# MH-M38-Bluetooth-audio-receiver-circuit.net
KiCad netlist of a schematic drawn in EAGLE
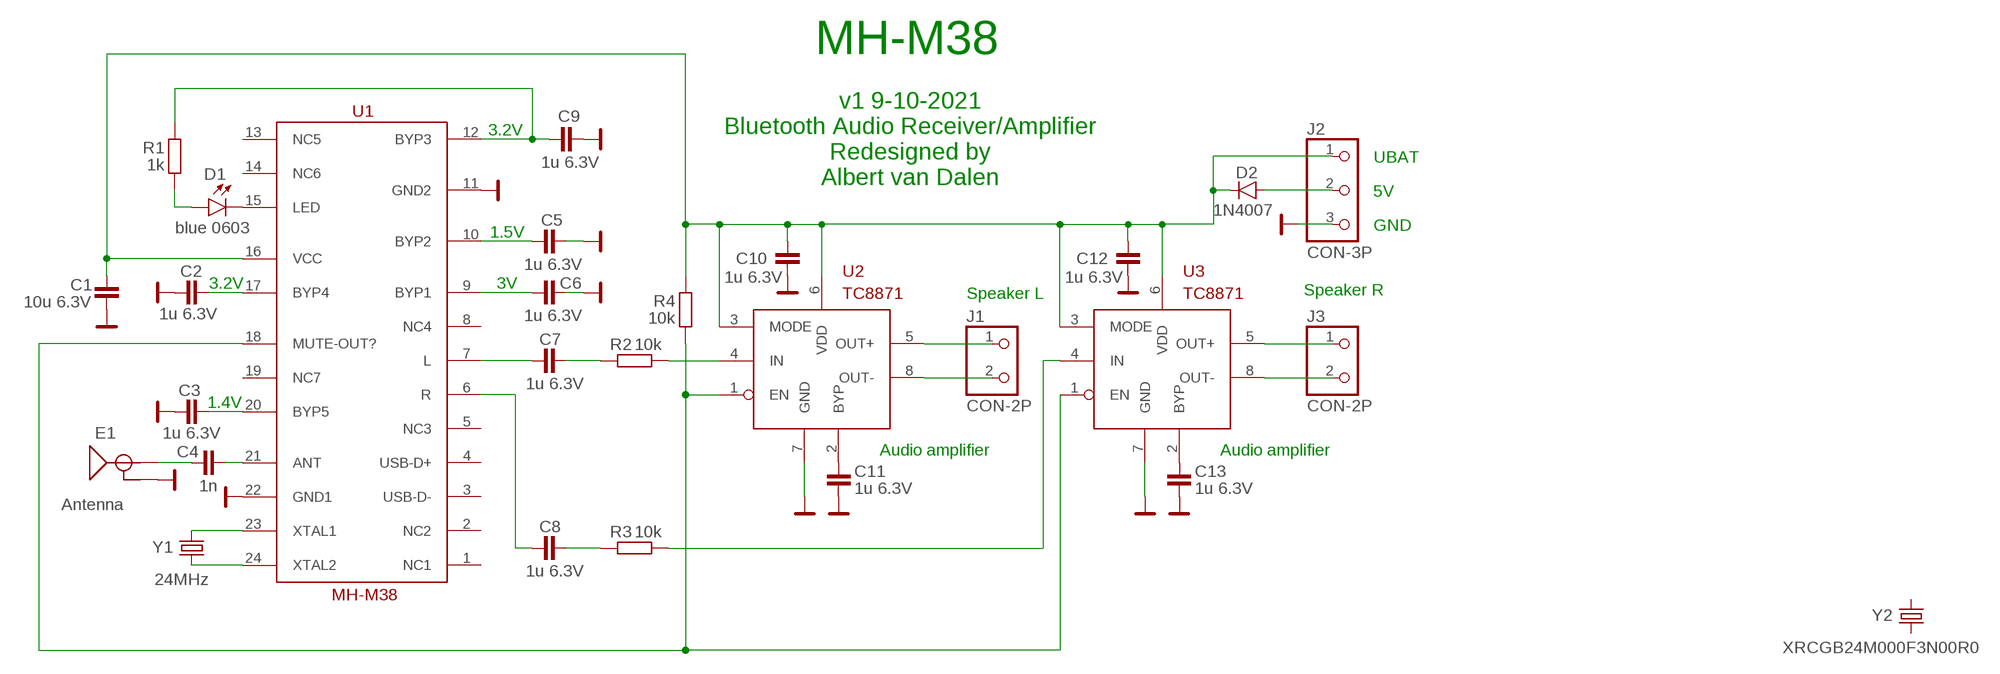
[diagram p0: schematic, sheet 1]

(export (version "E")
  (design (tool "Eeschema 10.0.6"))
  (components
    (comp (ref "C1")
      (value "10u 6.3V")
      (footprint "eagle-import:0603-SMALL")
      (libsource (lib "eagle-import") (part "SMD-C-0603-SMALL"))
    )
    (comp (ref "C2")
      (value "1u 6.3V")
      (footprint "eagle-import:0402-SMALL")
      (libsource (lib "eagle-import") (part "SMD-C-0402-SMALL"))
    )
    (comp (ref "C3")
      (value "1u 6.3V")
      (footprint "eagle-import:0402-SMALL")
      (libsource (lib "eagle-import") (part "SMD-C-0402-SMALL"))
    )
    (comp (ref "C4")
      (value "1n")
      (footprint "eagle-import:0402-SMALL")
      (libsource (lib "eagle-import") (part "SMD-C-0402-SMALL"))
    )
    (comp (ref "C5")
      (value "1u 6.3V")
      (footprint "eagle-import:0402-SMALL")
      (libsource (lib "eagle-import") (part "SMD-C-0402-SMALL"))
    )
    (comp (ref "C6")
      (value "1u 6.3V")
      (footprint "eagle-import:0402-SMALL")
      (libsource (lib "eagle-import") (part "SMD-C-0402-SMALL"))
    )
    (comp (ref "C7")
      (value "1u 6.3V")
      (footprint "eagle-import:0402-SMALL")
      (libsource (lib "eagle-import") (part "SMD-C-0402-SMALL"))
    )
    (comp (ref "C8")
      (value "1u 6.3V")
      (footprint "eagle-import:0402-SMALL")
      (libsource (lib "eagle-import") (part "SMD-C-0402-SMALL"))
    )
    (comp (ref "C9")
      (value "1u 6.3V")
      (footprint "eagle-import:0402-SMALL")
      (libsource (lib "eagle-import") (part "SMD-C-0402-SMALL"))
    )
    (comp (ref "C10")
      (value "1u 6.3V")
      (footprint "eagle-import:0402-SMALL")
      (libsource (lib "eagle-import") (part "SMD-C-0402-SMALL"))
    )
    (comp (ref "C11")
      (value "1u 6.3V")
      (footprint "eagle-import:0402-SMALL")
      (libsource (lib "eagle-import") (part "SMD-C-0402-SMALL"))
    )
    (comp (ref "C12")
      (value "1u 6.3V")
      (footprint "eagle-import:0402-SMALL")
      (libsource (lib "eagle-import") (part "SMD-C-0402-SMALL"))
    )
    (comp (ref "C13")
      (value "1u 6.3V")
      (footprint "eagle-import:0402-SMALL")
      (libsource (lib "eagle-import") (part "SMD-C-0402-SMALL"))
    )
    (comp (ref "D1")
      (value "blue 0603")
      (footprint "eagle-import:LED-0603")
      (libsource (lib "eagle-import") (part "LED"))
    )
    (comp (ref "D2")
      (value "1N4007")
      (footprint "eagle-import:SOD-323")
      (libsource (lib "eagle-import") (part "DIODE-SMD"))
    )
    (comp (ref "E1")
      (value "Antenna")
      (footprint "eagle-import:TRACE_ANTENNA_2.4GHZ_15.2MM")
      (libsource (lib "eagle-import") (part "ANTENNATRACE-15.2MM"))
    )
    (comp (ref "J1")
      (value "CON-2P")
      (footprint "eagle-import:JST-2")
      (libsource (lib "eagle-import") (part "CON-2P"))
    )
    (comp (ref "J2")
      (value "CON-3P")
      (footprint "eagle-import:JST-3")
      (libsource (lib "eagle-import") (part "CON-3P"))
    )
    (comp (ref "J3")
      (value "CON-2P")
      (footprint "eagle-import:JST-2")
      (libsource (lib "eagle-import") (part "CON-2P"))
    )
    (comp (ref "R1")
      (value "1k")
      (footprint "eagle-import:0402-SMALL")
      (libsource (lib "eagle-import") (part "SMD-R-0402-SMALL"))
    )
    (comp (ref "R2")
      (value "10k")
      (footprint "eagle-import:0402-SMALL")
      (libsource (lib "eagle-import") (part "SMD-R-0402-SMALL"))
    )
    (comp (ref "R3")
      (value "10k")
      (footprint "eagle-import:0402-SMALL")
      (libsource (lib "eagle-import") (part "SMD-R-0402-SMALL"))
    )
    (comp (ref "R4")
      (value "10k")
      (footprint "eagle-import:0402-SMALL")
      (libsource (lib "eagle-import") (part "SMD-R-0402-SMALL"))
    )
    (comp (ref "U1")
      (value "MH-M38")
      (footprint "eagle-import:TSSOP24-0.65-7.8X4.4MM")
      (libsource (lib "eagle-import") (part "MH-M38"))
    )
    (comp (ref "U2")
      (value "TC8871")
      (footprint "eagle-import:SO08")
      (libsource (lib "eagle-import") (part "TC8871"))
    )
    (comp (ref "U3")
      (value "TC8871")
      (footprint "eagle-import:SO08")
      (libsource (lib "eagle-import") (part "TC8871"))
    )
    (comp (ref "Y1")
      (value "24MHz")
      (footprint "eagle-import:FA-128")
      (libsource (lib "eagle-import") (part "CRYSTAL-SMD128"))
    )
    (comp (ref "Y2")
      (value "XRCGB24M000F3N00R0")
      (footprint "eagle-import:FA-128")
      (libsource (lib "eagle-import") (part "CRYSTAL-SMD128"))
    )
  )
  (nets
    (net (code "1") (name "GND") (class "Default")
      (node (ref "C1") (pin "2") (pinfunction "2_2") (pintype "passive"))
      (node (ref "C10") (pin "2") (pinfunction "2_2") (pintype "passive"))
      (node (ref "C11") (pin "2") (pinfunction "2_2") (pintype "passive"))
      (node (ref "C12") (pin "2") (pinfunction "2_2") (pintype "passive"))
      (node (ref "C13") (pin "2") (pinfunction "2_2") (pintype "passive"))
      (node (ref "C2") (pin "2") (pinfunction "2_2") (pintype "passive"))
      (node (ref "C3") (pin "2") (pinfunction "2_2") (pintype "passive"))
      (node (ref "C5") (pin "2") (pinfunction "2_2") (pintype "passive"))
      (node (ref "C6") (pin "2") (pinfunction "2_2") (pintype "passive"))
      (node (ref "C9") (pin "2") (pinfunction "2_2") (pintype "passive"))
      (node (ref "E1") (pin "GND") (pinfunction "GND_GND") (pintype "bidirectional"))
      (node (ref "J2") (pin "3") (pinfunction "3_3") (pintype "passive"))
      (node (ref "U1") (pin "11") (pinfunction "GND2_11") (pintype "bidirectional"))
      (node (ref "U1") (pin "22") (pinfunction "GND1_22") (pintype "bidirectional"))
      (node (ref "U2") (pin "7") (pinfunction "GND_7") (pintype "bidirectional"))
      (node (ref "U3") (pin "7") (pinfunction "GND_7") (pintype "bidirectional"))
    )
    (net (code "2") (name "Net-(C7-Pad2)") (class "Default")
      (node (ref "C7") (pin "2") (pinfunction "2_2") (pintype "passive"))
      (node (ref "R2") (pin "1") (pinfunction "1_1") (pintype "passive"))
    )
    (net (code "3") (name "Net-(C8-Pad2)") (class "Default")
      (node (ref "C8") (pin "2") (pinfunction "2_2") (pintype "passive"))
      (node (ref "R3") (pin "1") (pinfunction "1_1") (pintype "passive"))
    )
    (net (code "4") (name "Net-(D1-PadA)") (class "Default")
      (node (ref "D1") (pin "A") (pinfunction "A_A") (pintype "passive"))
      (node (ref "R1") (pin "1") (pinfunction "1_1") (pintype "passive"))
    )
    (net (code "5") (name "Net-(D2-PadA)") (class "Default")
      (node (ref "D2") (pin "A") (pinfunction "A_A") (pintype "passive"))
      (node (ref "J2") (pin "2") (pinfunction "2_2") (pintype "passive"))
    )
    (net (code "6") (name "Net-(E1-SIGNAL)") (class "Default")
      (node (ref "C4") (pin "2") (pinfunction "2_2") (pintype "passive"))
      (node (ref "E1") (pin "ANT") (pinfunction "SIGNAL_ANT") (pintype "bidirectional"))
    )
    (net (code "7") (name "Net-(U1-ANT)") (class "Default")
      (node (ref "C4") (pin "1") (pinfunction "1_1") (pintype "passive"))
      (node (ref "U1") (pin "21") (pinfunction "ANT_21") (pintype "bidirectional"))
    )
    (net (code "8") (name "Net-(U1-BYP1)") (class "Default")
      (node (ref "C6") (pin "1") (pinfunction "1_1") (pintype "passive"))
      (node (ref "U1") (pin "9") (pinfunction "BYP1_9") (pintype "bidirectional"))
    )
    (net (code "9") (name "Net-(U1-BYP2)") (class "Default")
      (node (ref "C5") (pin "1") (pinfunction "1_1") (pintype "passive"))
      (node (ref "U1") (pin "10") (pinfunction "BYP2_10") (pintype "bidirectional"))
    )
    (net (code "10") (name "Net-(U1-BYP3)") (class "Default")
      (node (ref "C9") (pin "1") (pinfunction "1_1") (pintype "passive"))
      (node (ref "R1") (pin "2") (pinfunction "2_2") (pintype "passive"))
      (node (ref "U1") (pin "12") (pinfunction "BYP3_12") (pintype "bidirectional"))
    )
    (net (code "11") (name "Net-(U1-BYP4)") (class "Default")
      (node (ref "C2") (pin "1") (pinfunction "1_1") (pintype "passive"))
      (node (ref "U1") (pin "17") (pinfunction "BYP4_17") (pintype "bidirectional"))
    )
    (net (code "12") (name "Net-(U1-BYP5)") (class "Default")
      (node (ref "C3") (pin "1") (pinfunction "1_1") (pintype "passive"))
      (node (ref "U1") (pin "20") (pinfunction "BYP5_20") (pintype "bidirectional"))
    )
    (net (code "13") (name "Net-(U1-L)") (class "Default")
      (node (ref "C7") (pin "1") (pinfunction "1_1") (pintype "passive"))
      (node (ref "U1") (pin "7") (pinfunction "L_7") (pintype "bidirectional"))
    )
    (net (code "14") (name "Net-(U1-LED)") (class "Default")
      (node (ref "D1") (pin "C") (pinfunction "C_C") (pintype "passive"))
      (node (ref "U1") (pin "15") (pinfunction "LED_15") (pintype "bidirectional"))
    )
    (net (code "15") (name "Net-(U1-MUTE-OUT?)") (class "Default")
      (node (ref "R4") (pin "1") (pinfunction "1_1") (pintype "passive"))
      (node (ref "U1") (pin "18") (pinfunction "MUTE-OUT?_18") (pintype "bidirectional"))
      (node (ref "U2") (pin "1") (pinfunction "EN_1") (pintype "bidirectional"))
      (node (ref "U3") (pin "1") (pinfunction "EN_1") (pintype "bidirectional"))
    )
    (net (code "16") (name "Net-(U1-R)") (class "Default")
      (node (ref "C8") (pin "1") (pinfunction "1_1") (pintype "passive"))
      (node (ref "U1") (pin "6") (pinfunction "R_6") (pintype "bidirectional"))
    )
    (net (code "17") (name "Net-(U1-VCC)") (class "Default")
      (node (ref "C1") (pin "1") (pinfunction "1_1") (pintype "passive"))
      (node (ref "C10") (pin "1") (pinfunction "1_1") (pintype "passive"))
      (node (ref "C12") (pin "1") (pinfunction "1_1") (pintype "passive"))
      (node (ref "D2") (pin "C") (pinfunction "C_C") (pintype "passive"))
      (node (ref "J2") (pin "1") (pinfunction "1_1") (pintype "passive"))
      (node (ref "R4") (pin "2") (pinfunction "2_2") (pintype "passive"))
      (node (ref "U1") (pin "16") (pinfunction "VCC_16") (pintype "bidirectional"))
      (node (ref "U2") (pin "3") (pinfunction "MODE_3") (pintype "bidirectional"))
      (node (ref "U2") (pin "6") (pinfunction "VDD_6") (pintype "bidirectional"))
      (node (ref "U3") (pin "3") (pinfunction "MODE_3") (pintype "bidirectional"))
      (node (ref "U3") (pin "6") (pinfunction "VDD_6") (pintype "bidirectional"))
    )
    (net (code "18") (name "Net-(U1-XTAL1)") (class "Default")
      (node (ref "U1") (pin "23") (pinfunction "XTAL1_23") (pintype "bidirectional"))
      (node (ref "Y1") (pin "3") (pinfunction "2_3") (pintype "bidirectional"))
    )
    (net (code "19") (name "Net-(U1-XTAL2)") (class "Default")
      (node (ref "U1") (pin "24") (pinfunction "XTAL2_24") (pintype "bidirectional"))
      (node (ref "Y1") (pin "1") (pinfunction "1_1") (pintype "bidirectional"))
    )
    (net (code "20") (name "Net-(U2-BYP)") (class "Default")
      (node (ref "C11") (pin "1") (pinfunction "1_1") (pintype "passive"))
      (node (ref "U2") (pin "2") (pinfunction "BYP_2") (pintype "bidirectional"))
    )
    (net (code "21") (name "Net-(U2-IN)") (class "Default")
      (node (ref "R2") (pin "2") (pinfunction "2_2") (pintype "passive"))
      (node (ref "U2") (pin "4") (pinfunction "IN_4") (pintype "bidirectional"))
    )
    (net (code "22") (name "Net-(U2-OUT+)") (class "Default")
      (node (ref "J1") (pin "1") (pinfunction "1_1") (pintype "passive"))
      (node (ref "U2") (pin "5") (pinfunction "OUT+_5") (pintype "bidirectional"))
    )
    (net (code "23") (name "Net-(U2-OUT-)") (class "Default")
      (node (ref "J1") (pin "2") (pinfunction "2_2") (pintype "passive"))
      (node (ref "U2") (pin "8") (pinfunction "OUT-_8") (pintype "bidirectional"))
    )
    (net (code "24") (name "Net-(U3-BYP)") (class "Default")
      (node (ref "C13") (pin "1") (pinfunction "1_1") (pintype "passive"))
      (node (ref "U3") (pin "2") (pinfunction "BYP_2") (pintype "bidirectional"))
    )
    (net (code "25") (name "Net-(U3-IN)") (class "Default")
      (node (ref "R3") (pin "2") (pinfunction "2_2") (pintype "passive"))
      (node (ref "U3") (pin "4") (pinfunction "IN_4") (pintype "bidirectional"))
    )
    (net (code "26") (name "Net-(U3-OUT+)") (class "Default")
      (node (ref "J3") (pin "1") (pinfunction "1_1") (pintype "passive"))
      (node (ref "U3") (pin "5") (pinfunction "OUT+_5") (pintype "bidirectional"))
    )
    (net (code "27") (name "Net-(U3-OUT-)") (class "Default")
      (node (ref "J3") (pin "2") (pinfunction "2_2") (pintype "passive"))
      (node (ref "U3") (pin "8") (pinfunction "OUT-_8") (pintype "bidirectional"))
    )
    (net (code "28") (name "unconnected-(U1-NC1-Pad1)") (class "Default")
      (node (ref "U1") (pin "1") (pinfunction "NC1_1") (pintype "bidirectional"))
    )
    (net (code "29") (name "unconnected-(U1-NC2-Pad2)") (class "Default")
      (node (ref "U1") (pin "2") (pinfunction "NC2_2") (pintype "bidirectional"))
    )
    (net (code "30") (name "unconnected-(U1-NC3-Pad5)") (class "Default")
      (node (ref "U1") (pin "5") (pinfunction "NC3_5") (pintype "bidirectional"))
    )
    (net (code "31") (name "unconnected-(U1-NC4-Pad8)") (class "Default")
      (node (ref "U1") (pin "8") (pinfunction "NC4_8") (pintype "bidirectional"))
    )
    (net (code "32") (name "unconnected-(U1-NC5-Pad13)") (class "Default")
      (node (ref "U1") (pin "13") (pinfunction "NC5_13") (pintype "bidirectional"))
    )
    (net (code "33") (name "unconnected-(U1-NC6-Pad14)") (class "Default")
      (node (ref "U1") (pin "14") (pinfunction "NC6_14") (pintype "bidirectional"))
    )
    (net (code "34") (name "unconnected-(U1-NC7-Pad19)") (class "Default")
      (node (ref "U1") (pin "19") (pinfunction "NC7_19") (pintype "bidirectional"))
    )
    (net (code "35") (name "unconnected-(U1-USB-D+-Pad4)") (class "Default")
      (node (ref "U1") (pin "4") (pinfunction "USB-D+_4") (pintype "bidirectional"))
    )
    (net (code "36") (name "unconnected-(U1-USB-D--Pad3)") (class "Default")
      (node (ref "U1") (pin "3") (pinfunction "USB-D-_3") (pintype "bidirectional"))
    )
    (net (code "37") (name "unconnected-(Y2-2-Pad3)") (class "Default")
      (node (ref "Y2") (pin "3") (pinfunction "2_3") (pintype "bidirectional"))
    )
    (net (code "38") (name "unconnected-(Y2-Pad1)") (class "Default")
      (node (ref "Y2") (pin "1") (pinfunction "1_1") (pintype "bidirectional"))
    )
  )
)
